# MCP3564_breakout.net
KiCad netlist of a schematic drawn in Altium Designer
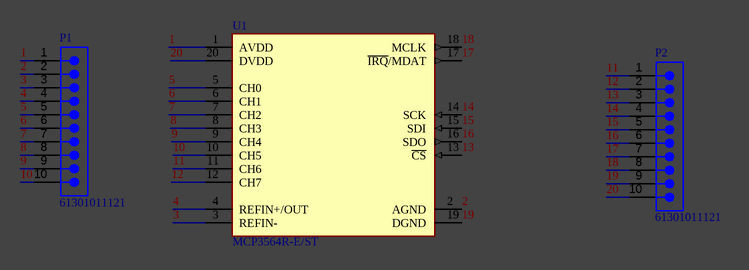
[diagram p0: MCP3564_breakout.SchDoc]

(export (version "E")
  (design (tool "Eeschema 10.0.6"))
  (components
    (comp (ref "P1")
      (value "61301011121")
      (footprint "61301011121")
      (libsource (lib "Altium Content Vault") (part "Header_Male_1R_10P"))
    )
    (comp (ref "P2")
      (value "61301011121")
      (footprint "61301011121")
      (libsource (lib "Altium Content Vault") (part "Header_Male_1R_10P"))
    )
    (comp (ref "U1")
      (value "MCP3564R-E/ST")
      (footprint "FP-C04-088-MFG")
      (description "MCP3564R-E/ST 8-Channel Single ADC Delta-Sigma 153.6ksps 24-bit Serial 20-Pin TSSOP Tube")
      (libsource (lib "Altium Content Vault") (part "0ac5b573d1d2d90c3815fbc455c1358"))
    )
  )
  (nets
    (net (code "1") (name "/1") (class "Default")
      (node (ref "P1") (pin "1") (pinfunction "1_1") (pintype "passive"))
      (node (ref "U1") (pin "1") (pinfunction "AVDD_1") (pintype "power_in"))
    )
    (net (code "2") (name "/2") (class "Default")
      (node (ref "P1") (pin "2") (pinfunction "2_2") (pintype "passive"))
      (node (ref "U1") (pin "2") (pinfunction "AGND_2") (pintype "power_in"))
    )
    (net (code "3") (name "/3") (class "Default")
      (node (ref "P1") (pin "3") (pinfunction "3_3") (pintype "passive"))
      (node (ref "U1") (pin "3") (pinfunction "REFIN-_3") (pintype "passive"))
    )
    (net (code "4") (name "/4") (class "Default")
      (node (ref "P1") (pin "4") (pinfunction "4_4") (pintype "passive"))
      (node (ref "U1") (pin "4") (pinfunction "REFIN+/OUT_4") (pintype "passive"))
    )
    (net (code "5") (name "/5") (class "Default")
      (node (ref "P1") (pin "5") (pinfunction "5_5") (pintype "passive"))
      (node (ref "U1") (pin "5") (pinfunction "CH0_5") (pintype "passive"))
    )
    (net (code "6") (name "/6") (class "Default")
      (node (ref "P1") (pin "6") (pinfunction "6_6") (pintype "passive"))
      (node (ref "U1") (pin "6") (pinfunction "CH1_6") (pintype "passive"))
    )
    (net (code "7") (name "/7") (class "Default")
      (node (ref "P1") (pin "7") (pinfunction "7_7") (pintype "passive"))
      (node (ref "U1") (pin "7") (pinfunction "CH2_7") (pintype "passive"))
    )
    (net (code "8") (name "/8") (class "Default")
      (node (ref "P1") (pin "8") (pinfunction "8_8") (pintype "passive"))
      (node (ref "U1") (pin "8") (pinfunction "CH3_8") (pintype "passive"))
    )
    (net (code "9") (name "/9") (class "Default")
      (node (ref "P1") (pin "9") (pinfunction "9_9") (pintype "passive"))
      (node (ref "U1") (pin "9") (pinfunction "CH4_9") (pintype "passive"))
    )
    (net (code "10") (name "/10") (class "Default")
      (node (ref "P1") (pin "10") (pinfunction "10_10") (pintype "passive"))
      (node (ref "U1") (pin "10") (pinfunction "CH5_10") (pintype "passive"))
    )
    (net (code "11") (name "/11") (class "Default")
      (node (ref "P2") (pin "1") (pinfunction "1_1") (pintype "passive"))
      (node (ref "U1") (pin "11") (pinfunction "CH6_11") (pintype "passive"))
    )
    (net (code "12") (name "/12") (class "Default")
      (node (ref "P2") (pin "2") (pinfunction "2_2") (pintype "passive"))
      (node (ref "U1") (pin "12") (pinfunction "CH7_12") (pintype "passive"))
    )
    (net (code "13") (name "/13") (class "Default")
      (node (ref "P2") (pin "3") (pinfunction "3_3") (pintype "passive"))
      (node (ref "U1") (pin "13") (pinfunction "~{CS}_13") (pintype "input"))
    )
    (net (code "14") (name "/14") (class "Default")
      (node (ref "P2") (pin "4") (pinfunction "4_4") (pintype "passive"))
      (node (ref "U1") (pin "14") (pinfunction "SCK_14") (pintype "input"))
    )
    (net (code "15") (name "/15") (class "Default")
      (node (ref "P2") (pin "5") (pinfunction "5_5") (pintype "passive"))
      (node (ref "U1") (pin "15") (pinfunction "SDI_15") (pintype "input"))
    )
    (net (code "16") (name "/16") (class "Default")
      (node (ref "P2") (pin "6") (pinfunction "6_6") (pintype "passive"))
      (node (ref "U1") (pin "16") (pinfunction "SDO_16") (pintype "output"))
    )
    (net (code "17") (name "/17") (class "Default")
      (node (ref "P2") (pin "7") (pinfunction "7_7") (pintype "passive"))
      (node (ref "U1") (pin "17") (pinfunction "~{IRQ}/MDAT_17") (pintype "output"))
    )
    (net (code "18") (name "/18") (class "Default")
      (node (ref "P2") (pin "8") (pinfunction "8_8") (pintype "passive"))
      (node (ref "U1") (pin "18") (pinfunction "MCLK_18") (pintype "output"))
    )
    (net (code "19") (name "/19") (class "Default")
      (node (ref "P2") (pin "9") (pinfunction "9_9") (pintype "passive"))
      (node (ref "U1") (pin "19") (pinfunction "DGND_19") (pintype "power_in"))
    )
    (net (code "20") (name "/20") (class "Default")
      (node (ref "P2") (pin "10") (pinfunction "10_10") (pintype "passive"))
      (node (ref "U1") (pin "20") (pinfunction "DVDD_20") (pintype "power_in"))
    )
  )
)
